# E32.net
KiCad netlist of a schematic drawn in Altium Designer
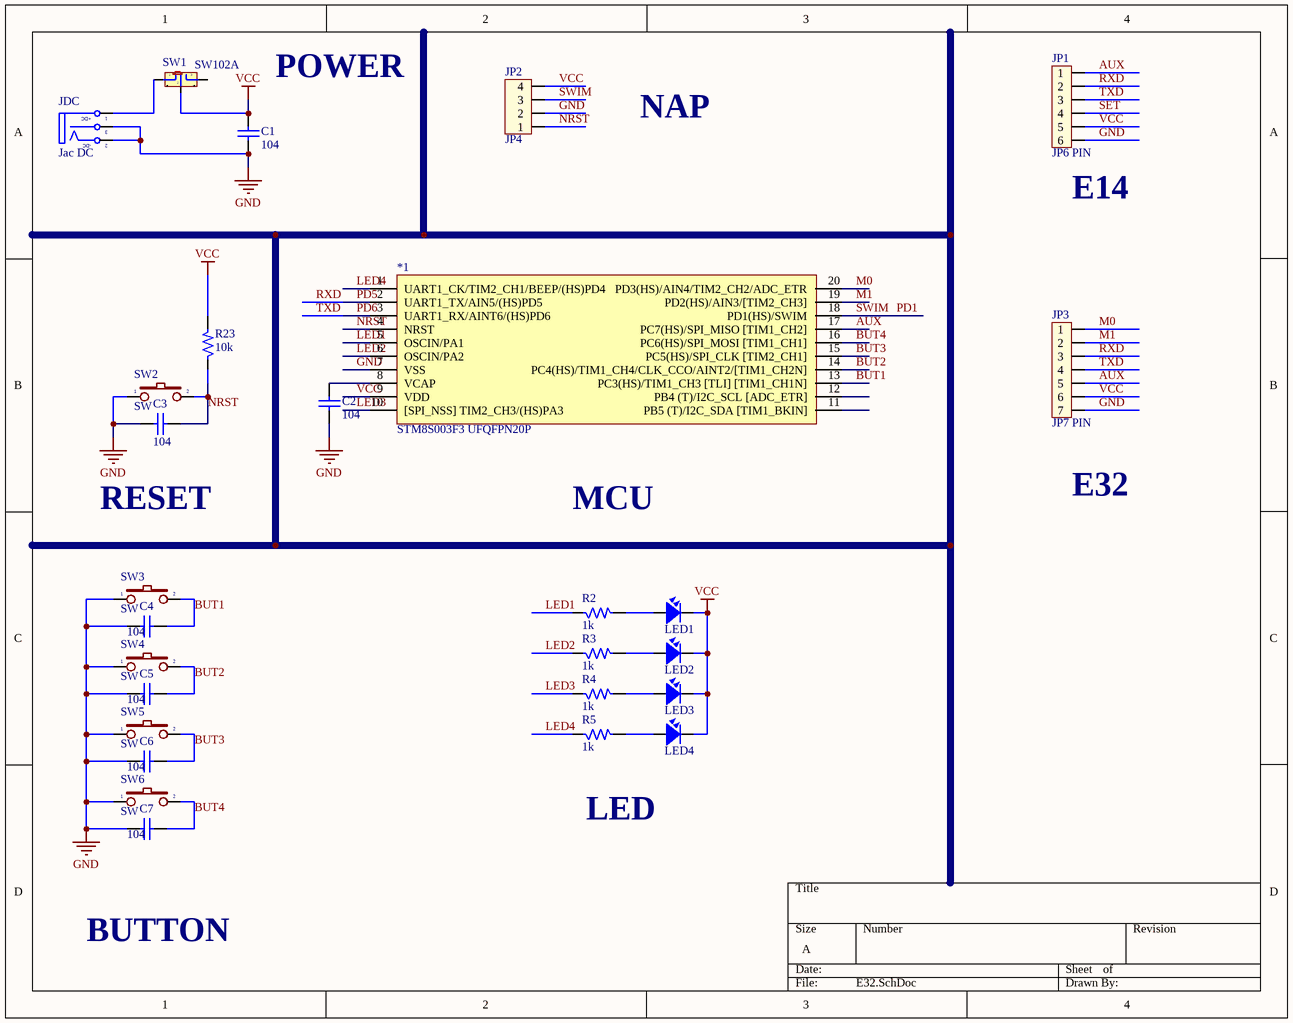
[diagram p0: E32.SchDoc]

(export (version "E")
  (design (tool "Eeschema 10.0.6"))
  (components
    (comp (ref "*1")
      (value "STM8S003F3 UFQFPN20P")
      (footprint "TSOP65-20BN")
      (libsource (lib "parafin9x") (part "STM8S003F3 UFQFPN20P"))
    )
    (comp (ref "C1")
      (value "104")
      (footprint "SM-CAP-0805")
      (description "Capacitor (Semiconductor SIM Model)")
      (libsource (lib "parafin9x") (part "Cap"))
    )
    (comp (ref "C2")
      (value "104")
      (footprint "SM-CAP-0805")
      (description "Capacitor (Semiconductor SIM Model)")
      (libsource (lib "parafin9x") (part "Cap"))
    )
    (comp (ref "C3")
      (value "104")
      (footprint "SM-CAP-0805")
      (description "Capacitor (Semiconductor SIM Model)")
      (libsource (lib "parafin9x") (part "Cap"))
    )
    (comp (ref "C4")
      (value "104")
      (footprint "SM-CAP-0805")
      (description "Capacitor (Semiconductor SIM Model)")
      (libsource (lib "parafin9x") (part "Cap"))
    )
    (comp (ref "C5")
      (value "104")
      (footprint "SM-CAP-0805")
      (description "Capacitor (Semiconductor SIM Model)")
      (libsource (lib "parafin9x") (part "Cap"))
    )
    (comp (ref "C6")
      (value "104")
      (footprint "SM-CAP-0805")
      (description "Capacitor (Semiconductor SIM Model)")
      (libsource (lib "parafin9x") (part "Cap"))
    )
    (comp (ref "C7")
      (value "104")
      (footprint "SM-CAP-0805")
      (description "Capacitor (Semiconductor SIM Model)")
      (libsource (lib "parafin9x") (part "Cap"))
    )
    (comp (ref "JDC")
      (value "Jac DC")
      (footprint "DC-IN")
      (description "Jac DC input")
      (libsource (lib "parafin9x") (part "DCIN"))
    )
    (comp (ref "JP1") (value "JP6 PIN") (footprint "JP6") (libsource (lib "parafin9x") (part "JP6")))
    (comp (ref "JP2")
      (value "JP4")
      (footprint "CON4")
      (description "Connector 4")
      (libsource (lib "parafin9x") (part "Con4"))
    )
    (comp (ref "JP3") (value "JP7 PIN") (footprint "JP7") (libsource (lib "parafin9x") (part "JP7")))
    (comp (ref "LED1")
      (value "LED")
      (footprint "LED-3")
      (description "LED Single colour Green and Red")
      (libsource (lib "parafin9x") (part "LED"))
    )
    (comp (ref "LED2")
      (value "LED")
      (footprint "LED-3")
      (description "LED Single colour Green and Red")
      (libsource (lib "parafin9x") (part "LED"))
    )
    (comp (ref "LED3")
      (value "LED")
      (footprint "LED-3")
      (description "LED Single colour Green and Red")
      (libsource (lib "parafin9x") (part "LED"))
    )
    (comp (ref "LED4")
      (value "LED")
      (footprint "LED-3")
      (description "LED Single colour Green and Red")
      (libsource (lib "parafin9x") (part "LED"))
    )
    (comp (ref "R2")
      (value "1k")
      (footprint "SM-RES-1206")
      (description "Resistor 1/4W")
      (libsource (lib "parafin9x") (part "R"))
    )
    (comp (ref "R3")
      (value "1k")
      (footprint "SM-RES-1206")
      (description "Resistor 1/4W")
      (libsource (lib "parafin9x") (part "R"))
    )
    (comp (ref "R4")
      (value "1k")
      (footprint "SM-RES-1206")
      (description "Resistor 1/4W")
      (libsource (lib "parafin9x") (part "R"))
    )
    (comp (ref "R5")
      (value "1k")
      (footprint "SM-RES-1206")
      (description "Resistor 1/4W")
      (libsource (lib "parafin9x") (part "R"))
    )
    (comp (ref "R23")
      (value "10k")
      (footprint "SM-RES-1206")
      (description "Resistor 1/4W")
      (libsource (lib "parafin9x") (part "R"))
    )
    (comp (ref "SW1")
      (value "SW102A")
      (footprint "SW102T")
      (description "Switch 102 on Broad")
      (libsource (lib "parafin9x") (part "SW102A"))
    )
    (comp (ref "SW2")
      (value "SW")
      (footprint "SW2")
      (description "Switch button 2 pin")
      (libsource (lib "parafin9x") (part "SW2"))
    )
    (comp (ref "SW3")
      (value "SW")
      (footprint "SW2")
      (description "Switch button 2 pin")
      (libsource (lib "parafin9x") (part "SW2"))
    )
    (comp (ref "SW4")
      (value "SW")
      (footprint "SW2")
      (description "Switch button 2 pin")
      (libsource (lib "parafin9x") (part "SW2"))
    )
    (comp (ref "SW5")
      (value "SW")
      (footprint "SW2")
      (description "Switch button 2 pin")
      (libsource (lib "parafin9x") (part "SW2"))
    )
    (comp (ref "SW6")
      (value "SW")
      (footprint "SW2")
      (description "Switch button 2 pin")
      (libsource (lib "parafin9x") (part "SW2"))
    )
  )
  (nets
    (net (code "1") (name "/AUX") (class "Default")
      (node (ref "*1") (pin "17") (pinfunction "PC7(HS)/SPI_MISO_[TIM1_CH2]_17") (pintype "passive"))
      (node (ref "JP1") (pin "1") (pinfunction "1_1") (pintype "passive"))
      (node (ref "JP3") (pin "5") (pinfunction "5_5") (pintype "passive"))
    )
    (net (code "2") (name "/BUT1") (class "Default")
      (node (ref "*1") (pin "13") (pinfunction "PC3(HS)/TIM1_CH3_[TLI]_[TIM1_CH1N]_13") (pintype "passive"))
      (node (ref "C4") (pin "2") (pinfunction "2_2") (pintype "passive"))
      (node (ref "SW3") (pin "2") (pinfunction "2_2") (pintype "passive"))
    )
    (net (code "3") (name "/BUT2") (class "Default")
      (node (ref "*1") (pin "14") (pinfunction "PC4(HS)/TIM1_CH4/CLK_CCO/AINT2/[TIM1_CH2N]_14") (pintype "passive"))
      (node (ref "C5") (pin "2") (pinfunction "2_2") (pintype "passive"))
      (node (ref "SW4") (pin "2") (pinfunction "2_2") (pintype "passive"))
    )
    (net (code "4") (name "/BUT3") (class "Default")
      (node (ref "*1") (pin "15") (pinfunction "PC5(HS)/SPI_CLK_[TIM2_CH1]_15") (pintype "passive"))
      (node (ref "C6") (pin "2") (pinfunction "2_2") (pintype "passive"))
      (node (ref "SW5") (pin "2") (pinfunction "2_2") (pintype "passive"))
    )
    (net (code "5") (name "/BUT4") (class "Default")
      (node (ref "*1") (pin "16") (pinfunction "PC6(HS)/SPI_MOSI_[TIM1_CH1]_16") (pintype "passive"))
      (node (ref "C7") (pin "2") (pinfunction "2_2") (pintype "passive"))
      (node (ref "SW6") (pin "2") (pinfunction "2_2") (pintype "passive"))
    )
    (net (code "6") (name "/LED1") (class "Default")
      (node (ref "*1") (pin "5") (pinfunction "OSCIN/PA1_5") (pintype "passive"))
      (node (ref "R2") (pin "1") (pinfunction "1_1") (pintype "passive"))
    )
    (net (code "7") (name "/LED2") (class "Default")
      (node (ref "*1") (pin "6") (pinfunction "OSCIN/PA2_6") (pintype "passive"))
      (node (ref "R3") (pin "1") (pinfunction "1_1") (pintype "passive"))
    )
    (net (code "8") (name "/LED3") (class "Default")
      (node (ref "*1") (pin "10") (pinfunction "[SPI_NSS]_TIM2_CH3/(HS)PA3_10") (pintype "passive"))
      (node (ref "R4") (pin "1") (pinfunction "1_1") (pintype "passive"))
    )
    (net (code "9") (name "/LED4") (class "Default")
      (node (ref "*1") (pin "1") (pinfunction "UART1_CK/TIM2_CH1/BEEP/(HS)PD4_1") (pintype "passive"))
      (node (ref "R5") (pin "1") (pinfunction "1_1") (pintype "passive"))
    )
    (net (code "10") (name "/M0") (class "Default")
      (node (ref "*1") (pin "20") (pinfunction "PD3(HS)/AIN4/TIM2_CH2/ADC_ETR_20") (pintype "passive"))
      (node (ref "JP3") (pin "1") (pinfunction "1_1") (pintype "passive"))
    )
    (net (code "11") (name "/M1") (class "Default")
      (node (ref "*1") (pin "19") (pinfunction "PD2(HS)/AIN3/[TIM2_CH3]_19") (pintype "passive"))
      (node (ref "JP3") (pin "2") (pinfunction "2_2") (pintype "passive"))
    )
    (net (code "12") (name "/NRST") (class "Default")
      (node (ref "*1") (pin "4") (pinfunction "NRST_4") (pintype "passive"))
      (node (ref "C3") (pin "2") (pinfunction "2_2") (pintype "passive"))
      (node (ref "JP2") (pin "1") (pinfunction "1_1") (pintype "passive"))
      (node (ref "R23") (pin "1") (pinfunction "1_1") (pintype "passive"))
      (node (ref "SW2") (pin "2") (pinfunction "2_2") (pintype "passive"))
    )
    (net (code "13") (name "/PD1") (class "Default")
      (node (ref "*1") (pin "18") (pinfunction "PD1(HS)/SWIM_18") (pintype "passive"))
      (node (ref "JP2") (pin "3") (pinfunction "3_3") (pintype "passive"))
    )
    (net (code "14") (name "/PD5") (class "Default")
      (node (ref "*1") (pin "2") (pinfunction "UART1_TX/AIN5/(HS)PD5_2") (pintype "passive"))
      (node (ref "JP1") (pin "2") (pinfunction "2_2") (pintype "passive"))
      (node (ref "JP3") (pin "3") (pinfunction "3_3") (pintype "passive"))
    )
    (net (code "15") (name "/PD6") (class "Default")
      (node (ref "*1") (pin "3") (pinfunction "UART1_RX/AINT6/(HS)PD6_3") (pintype "passive"))
      (node (ref "JP1") (pin "3") (pinfunction "3_3") (pintype "passive"))
      (node (ref "JP3") (pin "4") (pinfunction "4_4") (pintype "passive"))
    )
    (net (code "16") (name "/SET") (class "Default")
      (node (ref "JP1") (pin "4") (pinfunction "4_4") (pintype "passive"))
    )
    (net (code "17") (name "GND") (class "Default")
      (node (ref "*1") (pin "7") (pinfunction "VSS_7") (pintype "passive"))
      (node (ref "C1") (pin "1") (pinfunction "1_1") (pintype "passive"))
      (node (ref "C2") (pin "1") (pinfunction "1_1") (pintype "passive"))
      (node (ref "C3") (pin "1") (pinfunction "1_1") (pintype "passive"))
      (node (ref "C4") (pin "1") (pinfunction "1_1") (pintype "passive"))
      (node (ref "C5") (pin "1") (pinfunction "1_1") (pintype "passive"))
      (node (ref "C6") (pin "1") (pinfunction "1_1") (pintype "passive"))
      (node (ref "C7") (pin "1") (pinfunction "1_1") (pintype "passive"))
      (node (ref "JDC") (pin "2") (pinfunction "TN_2") (pintype "passive"))
      (node (ref "JDC") (pin "3") (pinfunction "S_3") (pintype "power_in"))
      (node (ref "JP1") (pin "6") (pinfunction "6_6") (pintype "passive"))
      (node (ref "JP2") (pin "2") (pinfunction "2_2") (pintype "passive"))
      (node (ref "JP3") (pin "7") (pinfunction "7_7") (pintype "passive"))
      (node (ref "SW2") (pin "1") (pinfunction "1_1") (pintype "passive"))
      (node (ref "SW3") (pin "1") (pinfunction "1_1") (pintype "passive"))
      (node (ref "SW4") (pin "1") (pinfunction "1_1") (pintype "passive"))
      (node (ref "SW5") (pin "1") (pinfunction "1_1") (pintype "passive"))
      (node (ref "SW6") (pin "1") (pinfunction "1_1") (pintype "passive"))
    )
    (net (code "18") (name "Net-(*1-VCAP)") (class "Default")
      (node (ref "*1") (pin "8") (pinfunction "VCAP_8") (pintype "passive"))
      (node (ref "C2") (pin "2") (pinfunction "2_2") (pintype "passive"))
    )
    (net (code "19") (name "Net-(JDC-T)") (class "Default")
      (node (ref "JDC") (pin "1") (pinfunction "T_1") (pintype "passive"))
      (node (ref "SW1") (pin "1") (pinfunction "1_1") (pintype "passive"))
    )
    (net (code "20") (name "Net-(LED1-Pad1)") (class "Default")
      (node (ref "LED1") (pin "1") (pinfunction "1_1") (pintype "passive"))
      (node (ref "R2") (pin "2") (pinfunction "2_2") (pintype "passive"))
    )
    (net (code "21") (name "Net-(LED2-Pad1)") (class "Default")
      (node (ref "LED2") (pin "1") (pinfunction "1_1") (pintype "passive"))
      (node (ref "R3") (pin "2") (pinfunction "2_2") (pintype "passive"))
    )
    (net (code "22") (name "Net-(LED3-Pad1)") (class "Default")
      (node (ref "LED3") (pin "1") (pinfunction "1_1") (pintype "passive"))
      (node (ref "R4") (pin "2") (pinfunction "2_2") (pintype "passive"))
    )
    (net (code "23") (name "Net-(LED4-Pad1)") (class "Default")
      (node (ref "LED4") (pin "1") (pinfunction "1_1") (pintype "passive"))
      (node (ref "R5") (pin "2") (pinfunction "2_2") (pintype "passive"))
    )
    (net (code "24") (name "VCC") (class "Default")
      (node (ref "*1") (pin "9") (pinfunction "VDD_9") (pintype "passive"))
      (node (ref "C1") (pin "2") (pinfunction "2_2") (pintype "passive"))
      (node (ref "JP1") (pin "5") (pinfunction "5_5") (pintype "passive"))
      (node (ref "JP2") (pin "4") (pinfunction "4_4") (pintype "passive"))
      (node (ref "JP3") (pin "6") (pinfunction "6_6") (pintype "passive"))
      (node (ref "LED1") (pin "2") (pinfunction "2_2") (pintype "passive"))
      (node (ref "LED2") (pin "2") (pinfunction "2_2") (pintype "passive"))
      (node (ref "LED3") (pin "2") (pinfunction "2_2") (pintype "passive"))
      (node (ref "LED4") (pin "2") (pinfunction "2_2") (pintype "passive"))
      (node (ref "R23") (pin "2") (pinfunction "2_2") (pintype "passive"))
      (node (ref "SW1") (pin "2") (pinfunction "2_2") (pintype "passive"))
    )
    (net (code "25") (name "unconnected-(*1-PB4_(T){slash}I2C_SCL_[ADC_ETR]-Pad12)") (class "Default")
      (node (ref "*1") (pin "12") (pinfunction "PB4_(T)/I2C_SCL_[ADC_ETR]_12") (pintype "passive"))
    )
    (net (code "26") (name "unconnected-(*1-PB5_(T){slash}I2C_SDA_[TIM1_BKIN]-Pad11)") (class "Default")
      (node (ref "*1") (pin "11") (pinfunction "PB5_(T)/I2C_SDA_[TIM1_BKIN]_11") (pintype "passive"))
    )
    (net (code "27") (name "unconnected-(SW1-Pad3)") (class "Default")
      (node (ref "SW1") (pin "3") (pinfunction "3_3") (pintype "passive"))
    )
    (net (code "28") (name "unconnected-(SW1-Pad4)") (class "Default")
      (node (ref "SW1") (pin "4") (pinfunction "4_4") (pintype "passive"))
    )
    (net (code "29") (name "unconnected-(SW1-Pad5)") (class "Default")
      (node (ref "SW1") (pin "5") (pinfunction "5_5") (pintype "passive"))
    )
  )
)
